# asynchronous.net
KiCad netlist of a schematic drawn in Altium Designer
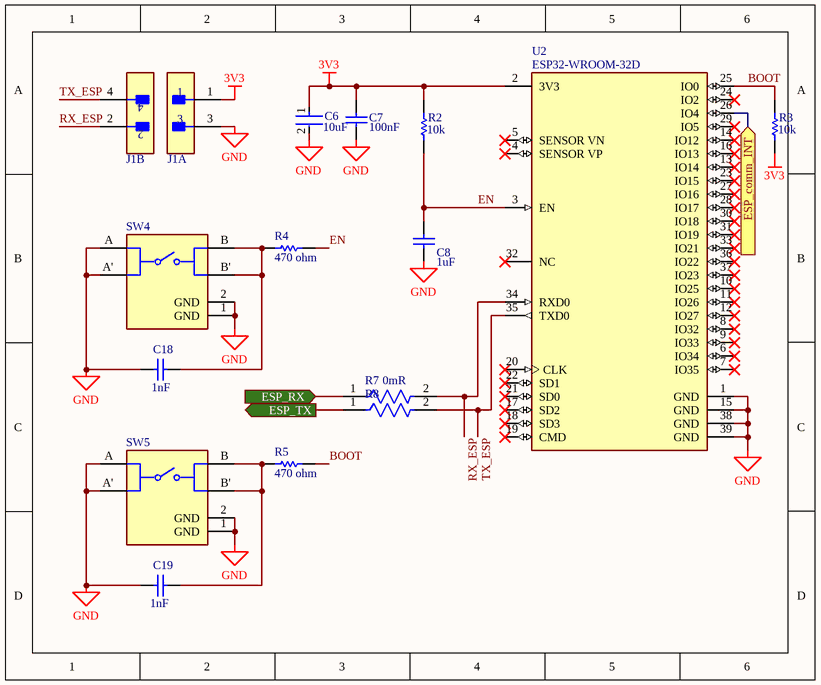
[diagram p0: asynchronous.SchDoc]

(export (version "E")
  (design (tool "Eeschema 10.0.6"))
  (components
    (comp (ref "C6")
      (value "1206YD106KAT2A")
      (footprint "FP-1206-L_3_2_0_2-W_1_6_0-IPC_B")
      (description "General Purpose Ceramic Capacitor, 1206, 10uF, 10%, X5R, 15%, 16V")
      (fields
        (field (name "TOLERANCE") "10%")
        (field (name "CAPACITANCE") "10uF")
        (field (name "VOLTAGE") "16V")
      )
      (libsource (lib "Altium Content Vault") (part "02cd4be3c70576c341d710602a673aa"))
    )
    (comp (ref "C7")
      (value "100nF")
      (footprint "CAPC2013X140X50LL20T25")
      (fields
        (field (name "MANUFACTURER") "AVX Interconnect / Elco")
        (field (name "PART NUMBER") "08055F104KAT2A")
      )
      (libsource (lib "Altium Content Vault") (part "CAP"))
    )
    (comp (ref "C8")
      (value "C0805C105K4PACTU")
      (footprint "CAPC2013X145X50LL20T25")
      (fields (field (name "MANUFACTURER") "Kemet") (field (name "PARAMETER 1") "1uF"))
      (libsource (lib "Altium Content Vault") (part "CAP"))
    )
    (comp (ref "C18")
      (value "VJ0805D102KXAAJ")
      (footprint "CAPC2013X145X48LL20T23")
      (fields (field (name "MANUFACTURER") "Vitramon") (field (name "PARAMETER 1") "1nF"))
      (libsource (lib "Altium Content Vault") (part "CAP"))
    )
    (comp (ref "C19")
      (value "VJ0805D102KXAAJ")
      (footprint "CAPC2013X145X48LL20T23")
      (fields (field (name "MANUFACTURER") "Vitramon") (field (name "PARAMETER 1") "1nF"))
      (libsource (lib "Altium Content Vault") (part "CAP"))
    )
    (comp (ref "J1")
      (value "PEC02DABN")
      (footprint "FP-PEC02DABN-MFG")
      (description "CONN HEADER VERT 4POS 2.54MM")
      (libsource (lib "") (part "1621473add15499e993d6bbd36d0f06_1"))
    )
    (comp (ref "R2")
      (value "RC0805FR-0710KL")
      (footprint "RESC2013X60X35NL10T20")
      (description "Chip Resistor, 10 KOhm, +/- 1%, 0.125 W, -55 to 155 degC, 0805 (2012 Metric), RoHS, Tape and Reel")
      (fields (field (name "MANUFACTURER") "Yageo") (field (name "PARAMETER 1") "10k"))
      (libsource (lib "Altium Content Vault") (part "RES-2"))
    )
    (comp (ref "R3")
      (value "RC0805FR-0710KL")
      (footprint "RESC2013X60X35NL10T20")
      (description "Chip Resistor, 10 KOhm, +/- 1%, 0.125 W, -55 to 155 degC, 0805 (2012 Metric), RoHS, Tape and Reel")
      (fields (field (name "MANUFACTURER") "Yageo") (field (name "PARAMETER 1") "10k"))
      (libsource (lib "Altium Content Vault") (part "RES-2"))
    )
    (comp (ref "R4")
      (value "CRCW0805470RFKEA")
      (footprint "RESC2013X50X30LL20T20")
      (fields (field (name "MANUFACTURER") "Vishay Dale") (field (name "PARAMETER 1") "470 ohm"))
      (libsource (lib "Altium Content Vault") (part "RES"))
    )
    (comp (ref "R5")
      (value "CRCW0805470RFKEA")
      (footprint "RESC2013X50X30LL20T20")
      (fields (field (name "MANUFACTURER") "Vishay Dale") (field (name "PARAMETER 1") "470 ohm"))
      (libsource (lib "Altium Content Vault") (part "RES"))
    )
    (comp (ref "R7")
      (value "CR0805-J/-000ELF")
      (footprint "FP-CR0805-IPC_C")
      (description "Thick Film Chip Resistors 0805 0Ω 0.125W 5%")
      (fields (field (name "RESISTANCE") "0mR") (field (name "TOLERANCE") "5%"))
      (libsource (lib "Altium Content Vault") (part "1029c3af85768c4190bb7ad29bc67b5"))
    )
    (comp (ref "R8")
      (value "CR0805-J/-000ELF")
      (footprint "FP-CR0805-IPC_C")
      (description "Thick Film Chip Resistors 0805 0Ω 0.125W 5%")
      (fields (field (name "TOLERANCE") "5%"))
      (libsource (lib "Altium Content Vault") (part "1029c3af85768c4190bb7ad29bc67b5"))
    )
    (comp (ref "SW4")
      (value "EVQ-PLMA15")
      (footprint "FP-EVQ-PLMA15-MFG")
      (description "SWITCH TACTILE SPST-NO 0.02A 15V")
      (fields
        (field (name "OCTOPART") "https://octopart.com/evq-plma15-panasonic-39850235")
        (field (name "MANUFACTURER") "Panasonic Electronic Components")
      )
      (libsource (lib "Altium Content Vault") (part "fc7b47d2e4813f0909612a6c4f63938"))
    )
    (comp (ref "SW5")
      (value "EVQ-PLMA15")
      (footprint "FP-EVQ-PLMA15-MFG")
      (description "SWITCH TACTILE SPST-NO 0.02A 15V")
      (fields
        (field (name "OCTOPART") "https://octopart.com/evq-plma15-panasonic-39850235")
        (field (name "MANUFACTURER") "Panasonic Electronic Components")
      )
      (libsource (lib "Altium Content Vault") (part "fc7b47d2e4813f0909612a6c4f63938"))
    )
    (comp (ref "U2")
      (value "ESP32-WROOM-32D")
      (footprint "FP-ESP32-WROOM-32D-MFG")
      (description "WIFI MODULE 32MBITS SPI FLASH")
      (fields
        (field (name "OCTOPART") "https://octopart.com/esp32-wroom-32d-espressif+systems-91040050")
        (field (name "MANUFACTURER") "Espressif Systems")
      )
      (libsource (lib "Altium Content Vault") (part "a031a76f8c27026a7a7f4657ff233a3"))
    )
  )
  (nets
    (net (code "1") (name "/BOOT") (class "Default")
      (node (ref "R3") (pin "2") (pinfunction "2_2") (pintype "passive"))
      (node (ref "R5") (pin "2") (pinfunction "2_2") (pintype "passive"))
      (node (ref "U2") (pin "25") (pinfunction "IO0_25") (pintype "bidirectional"))
    )
    (net (code "2") (name "/EN") (class "Default")
      (node (ref "C8") (pin "2") (pinfunction "2_2") (pintype "passive"))
      (node (ref "R2") (pin "1") (pinfunction "1_1") (pintype "passive"))
      (node (ref "R4") (pin "2") (pinfunction "2_2") (pintype "passive"))
      (node (ref "U2") (pin "3") (pinfunction "EN_3") (pintype "input"))
    )
    (net (code "3") (name "/ESP_RX") (class "Default")
      (node (ref "R7") (pin "1") (pinfunction "1_1") (pintype "passive"))
    )
    (net (code "4") (name "/ESP_TX") (class "Default")
      (node (ref "R8") (pin "1") (pinfunction "1_1") (pintype "passive"))
    )
    (net (code "5") (name "/ESP_comm_INT") (class "Default")
      (node (ref "U2") (pin "26") (pinfunction "IO4_26") (pintype "bidirectional"))
    )
    (net (code "6") (name "/RX_ESP") (class "Default")
      (node (ref "J1") (pin "2") (pinfunction "2_2") (pintype "passive"))
      (node (ref "R7") (pin "2") (pinfunction "2_2") (pintype "passive"))
      (node (ref "U2") (pin "34") (pinfunction "RXD0_34") (pintype "input"))
    )
    (net (code "7") (name "/TX_ESP") (class "Default")
      (node (ref "J1") (pin "4") (pinfunction "4_4") (pintype "passive"))
      (node (ref "R8") (pin "2") (pinfunction "2_2") (pintype "passive"))
      (node (ref "U2") (pin "35") (pinfunction "TXD0_35") (pintype "output"))
    )
    (net (code "8") (name "3V3") (class "Default")
      (node (ref "C6") (pin "1") (pinfunction "1_1") (pintype "passive"))
      (node (ref "C7") (pin "2") (pinfunction "2_2") (pintype "passive"))
      (node (ref "J1") (pin "1") (pinfunction "1_1") (pintype "passive"))
      (node (ref "R2") (pin "2") (pinfunction "2_2") (pintype "passive"))
      (node (ref "R3") (pin "1") (pinfunction "1_1") (pintype "passive"))
      (node (ref "U2") (pin "2") (pinfunction "3V3_2") (pintype "power_in"))
    )
    (net (code "9") (name "GND") (class "Default")
      (node (ref "C18") (pin "1") (pinfunction "1_1") (pintype "passive"))
      (node (ref "C19") (pin "1") (pinfunction "1_1") (pintype "passive"))
      (node (ref "C6") (pin "2") (pinfunction "2_2") (pintype "passive"))
      (node (ref "C7") (pin "1") (pinfunction "1_1") (pintype "passive"))
      (node (ref "C8") (pin "1") (pinfunction "1_1") (pintype "passive"))
      (node (ref "J1") (pin "3") (pinfunction "3_3") (pintype "passive"))
      (node (ref "SW4") (pin "1") (pinfunction "GND_1") (pintype "power_in"))
      (node (ref "SW4") (pin "2") (pinfunction "GND_2") (pintype "power_in"))
      (node (ref "SW4") (pin "A") (pinfunction "A_A") (pintype "passive"))
      (node (ref "SW4") (pin "A'") (pinfunction "A'_A'") (pintype "passive"))
      (node (ref "SW5") (pin "1") (pinfunction "GND_1") (pintype "power_in"))
      (node (ref "SW5") (pin "2") (pinfunction "GND_2") (pintype "power_in"))
      (node (ref "SW5") (pin "A") (pinfunction "A_A") (pintype "passive"))
      (node (ref "SW5") (pin "A'") (pinfunction "A'_A'") (pintype "passive"))
      (node (ref "U2") (pin "1") (pinfunction "GND_1") (pintype "power_in"))
      (node (ref "U2") (pin "15") (pinfunction "GND_15") (pintype "power_in"))
      (node (ref "U2") (pin "38") (pinfunction "GND_38") (pintype "power_in"))
      (node (ref "U2") (pin "39") (pinfunction "GND_39") (pintype "power_in"))
    )
    (net (code "10") (name "Net-(C18-Pad2)") (class "Default")
      (node (ref "C18") (pin "2") (pinfunction "2_2") (pintype "passive"))
      (node (ref "R4") (pin "1") (pinfunction "1_1") (pintype "passive"))
      (node (ref "SW4") (pin "B") (pinfunction "B_B") (pintype "passive"))
      (node (ref "SW4") (pin "B'") (pinfunction "B'_B'") (pintype "passive"))
    )
    (net (code "11") (name "Net-(C19-Pad2)") (class "Default")
      (node (ref "C19") (pin "2") (pinfunction "2_2") (pintype "passive"))
      (node (ref "R5") (pin "1") (pinfunction "1_1") (pintype "passive"))
      (node (ref "SW5") (pin "B") (pinfunction "B_B") (pintype "passive"))
      (node (ref "SW5") (pin "B'") (pinfunction "B'_B'") (pintype "passive"))
    )
    (net (code "12") (name "unconnected-(U2-CLK-Pad20)") (class "Default")
      (node (ref "U2") (pin "20") (pinfunction "CLK_20") (pintype "input+no_connect"))
    )
    (net (code "13") (name "unconnected-(U2-CMD-Pad19)") (class "Default")
      (node (ref "U2") (pin "19") (pinfunction "CMD_19") (pintype "bidirectional+no_connect"))
    )
    (net (code "14") (name "unconnected-(U2-IO2-Pad24)") (class "Default")
      (node (ref "U2") (pin "24") (pinfunction "IO2_24") (pintype "bidirectional+no_connect"))
    )
    (net (code "15") (name "unconnected-(U2-IO5-Pad29)") (class "Default")
      (node (ref "U2") (pin "29") (pinfunction "IO5_29") (pintype "bidirectional+no_connect"))
    )
    (net (code "16") (name "unconnected-(U2-IO12-Pad14)") (class "Default")
      (node (ref "U2") (pin "14") (pinfunction "IO12_14") (pintype "bidirectional+no_connect"))
    )
    (net (code "17") (name "unconnected-(U2-IO13-Pad16)") (class "Default")
      (node (ref "U2") (pin "16") (pinfunction "IO13_16") (pintype "bidirectional+no_connect"))
    )
    (net (code "18") (name "unconnected-(U2-IO14-Pad13)") (class "Default")
      (node (ref "U2") (pin "13") (pinfunction "IO14_13") (pintype "bidirectional+no_connect"))
    )
    (net (code "19") (name "unconnected-(U2-IO15-Pad23)") (class "Default")
      (node (ref "U2") (pin "23") (pinfunction "IO15_23") (pintype "bidirectional+no_connect"))
    )
    (net (code "20") (name "unconnected-(U2-IO16-Pad27)") (class "Default")
      (node (ref "U2") (pin "27") (pinfunction "IO16_27") (pintype "bidirectional+no_connect"))
    )
    (net (code "21") (name "unconnected-(U2-IO17-Pad28)") (class "Default")
      (node (ref "U2") (pin "28") (pinfunction "IO17_28") (pintype "bidirectional+no_connect"))
    )
    (net (code "22") (name "unconnected-(U2-IO18-Pad30)") (class "Default")
      (node (ref "U2") (pin "30") (pinfunction "IO18_30") (pintype "bidirectional+no_connect"))
    )
    (net (code "23") (name "unconnected-(U2-IO19-Pad31)") (class "Default")
      (node (ref "U2") (pin "31") (pinfunction "IO19_31") (pintype "bidirectional+no_connect"))
    )
    (net (code "24") (name "unconnected-(U2-IO21-Pad33)") (class "Default")
      (node (ref "U2") (pin "33") (pinfunction "IO21_33") (pintype "bidirectional+no_connect"))
    )
    (net (code "25") (name "unconnected-(U2-IO22-Pad36)") (class "Default")
      (node (ref "U2") (pin "36") (pinfunction "IO22_36") (pintype "bidirectional+no_connect"))
    )
    (net (code "26") (name "unconnected-(U2-IO23-Pad37)") (class "Default")
      (node (ref "U2") (pin "37") (pinfunction "IO23_37") (pintype "bidirectional+no_connect"))
    )
    (net (code "27") (name "unconnected-(U2-IO25-Pad10)") (class "Default")
      (node (ref "U2") (pin "10") (pinfunction "IO25_10") (pintype "bidirectional+no_connect"))
    )
    (net (code "28") (name "unconnected-(U2-IO26-Pad11)") (class "Default")
      (node (ref "U2") (pin "11") (pinfunction "IO26_11") (pintype "bidirectional+no_connect"))
    )
    (net (code "29") (name "unconnected-(U2-IO27-Pad12)") (class "Default")
      (node (ref "U2") (pin "12") (pinfunction "IO27_12") (pintype "bidirectional+no_connect"))
    )
    (net (code "30") (name "unconnected-(U2-IO32-Pad8)") (class "Default")
      (node (ref "U2") (pin "8") (pinfunction "IO32_8") (pintype "bidirectional+no_connect"))
    )
    (net (code "31") (name "unconnected-(U2-IO33-Pad9)") (class "Default")
      (node (ref "U2") (pin "9") (pinfunction "IO33_9") (pintype "bidirectional+no_connect"))
    )
    (net (code "32") (name "unconnected-(U2-IO34-Pad6)") (class "Default")
      (node (ref "U2") (pin "6") (pinfunction "IO34_6") (pintype "bidirectional+no_connect"))
    )
    (net (code "33") (name "unconnected-(U2-IO35-Pad7)") (class "Default")
      (node (ref "U2") (pin "7") (pinfunction "IO35_7") (pintype "bidirectional+no_connect"))
    )
    (net (code "34") (name "unconnected-(U2-NC-Pad32)") (class "Default")
      (node (ref "U2") (pin "32") (pinfunction "NC_32") (pintype "passive+no_connect"))
    )
    (net (code "35") (name "unconnected-(U2-SD0-Pad21)") (class "Default")
      (node (ref "U2") (pin "21") (pinfunction "SD0_21") (pintype "bidirectional+no_connect"))
    )
    (net (code "36") (name "unconnected-(U2-SD1-Pad22)") (class "Default")
      (node (ref "U2") (pin "22") (pinfunction "SD1_22") (pintype "bidirectional+no_connect"))
    )
    (net (code "37") (name "unconnected-(U2-SD2-Pad17)") (class "Default")
      (node (ref "U2") (pin "17") (pinfunction "SD2_17") (pintype "bidirectional+no_connect"))
    )
    (net (code "38") (name "unconnected-(U2-SD3-Pad18)") (class "Default")
      (node (ref "U2") (pin "18") (pinfunction "SD3_18") (pintype "bidirectional+no_connect"))
    )
    (net (code "39") (name "unconnected-(U2-SENSOR_VN-Pad5)") (class "Default")
      (node (ref "U2") (pin "5") (pinfunction "SENSOR_VN_5") (pintype "bidirectional+no_connect"))
    )
    (net (code "40") (name "unconnected-(U2-SENSOR_VP-Pad4)") (class "Default")
      (node (ref "U2") (pin "4") (pinfunction "SENSOR_VP_4") (pintype "bidirectional+no_connect"))
    )
  )
)
